# Communication.net
KiCad netlist of a schematic drawn in EAGLE
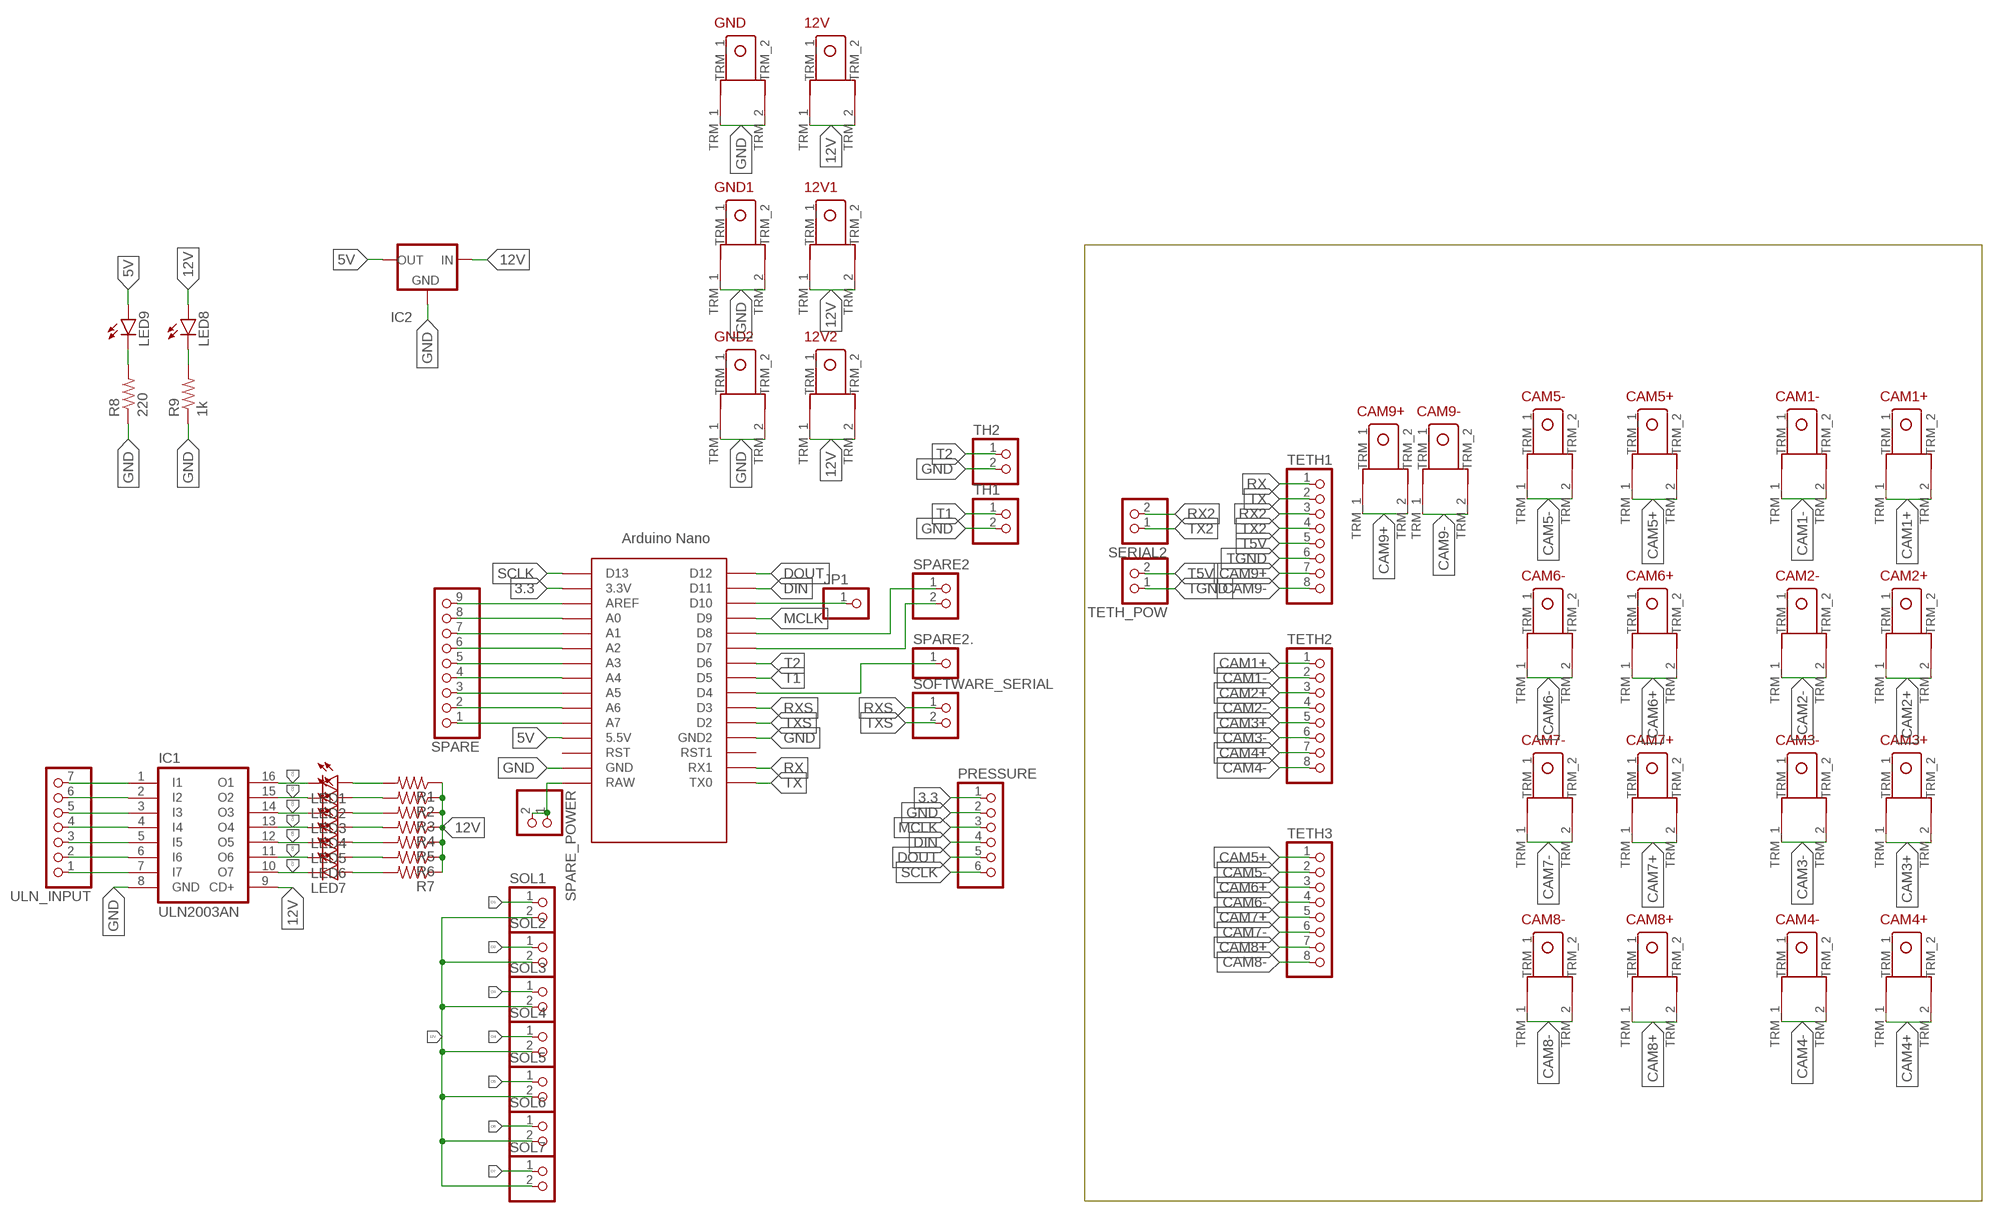
[diagram p0: schematic, sheet 1]

(export (version "E")
  (design (tool "Eeschema 10.0.6"))
  (components
    (comp (ref "12V")
      (value "TERMINAL_EDITED")
      (footprint "eagle-import:TERMINAL_EDITED")
      (libsource (lib "eagle-import") (part "TERMINAL_EDITED"))
    )
    (comp (ref "12V1")
      (value "TERMINAL_EDITED")
      (footprint "eagle-import:TERMINAL_EDITED")
      (libsource (lib "eagle-import") (part "TERMINAL_EDITED"))
    )
    (comp (ref "12V2")
      (value "TERMINAL_EDITED")
      (footprint "eagle-import:TERMINAL_EDITED")
      (libsource (lib "eagle-import") (part "TERMINAL_EDITED"))
    )
    (comp (ref "CAM1+")
      (value "TERMINAL_EDITED")
      (footprint "eagle-import:TERMINAL_EDITED")
      (libsource (lib "eagle-import") (part "TERMINAL_EDITED"))
    )
    (comp (ref "CAM1-")
      (value "TERMINAL_EDITED")
      (footprint "eagle-import:TERMINAL_EDITED")
      (libsource (lib "eagle-import") (part "TERMINAL_EDITED"))
    )
    (comp (ref "CAM2+")
      (value "TERMINAL_EDITED")
      (footprint "eagle-import:TERMINAL_EDITED")
      (libsource (lib "eagle-import") (part "TERMINAL_EDITED"))
    )
    (comp (ref "CAM2-")
      (value "TERMINAL_EDITED")
      (footprint "eagle-import:TERMINAL_EDITED")
      (libsource (lib "eagle-import") (part "TERMINAL_EDITED"))
    )
    (comp (ref "CAM3+")
      (value "TERMINAL_EDITED")
      (footprint "eagle-import:TERMINAL_EDITED")
      (libsource (lib "eagle-import") (part "TERMINAL_EDITED"))
    )
    (comp (ref "CAM3-")
      (value "TERMINAL_EDITED")
      (footprint "eagle-import:TERMINAL_EDITED")
      (libsource (lib "eagle-import") (part "TERMINAL_EDITED"))
    )
    (comp (ref "CAM4+")
      (value "TERMINAL_EDITED")
      (footprint "eagle-import:TERMINAL_EDITED")
      (libsource (lib "eagle-import") (part "TERMINAL_EDITED"))
    )
    (comp (ref "CAM4-")
      (value "TERMINAL_EDITED")
      (footprint "eagle-import:TERMINAL_EDITED")
      (libsource (lib "eagle-import") (part "TERMINAL_EDITED"))
    )
    (comp (ref "CAM5+")
      (value "TERMINAL_EDITED")
      (footprint "eagle-import:TERMINAL_EDITED")
      (libsource (lib "eagle-import") (part "TERMINAL_EDITED"))
    )
    (comp (ref "CAM5-")
      (value "TERMINAL_EDITED")
      (footprint "eagle-import:TERMINAL_EDITED")
      (libsource (lib "eagle-import") (part "TERMINAL_EDITED"))
    )
    (comp (ref "CAM6+")
      (value "TERMINAL_EDITED")
      (footprint "eagle-import:TERMINAL_EDITED")
      (libsource (lib "eagle-import") (part "TERMINAL_EDITED"))
    )
    (comp (ref "CAM6-")
      (value "TERMINAL_EDITED")
      (footprint "eagle-import:TERMINAL_EDITED")
      (libsource (lib "eagle-import") (part "TERMINAL_EDITED"))
    )
    (comp (ref "CAM7+")
      (value "TERMINAL_EDITED")
      (footprint "eagle-import:TERMINAL_EDITED")
      (libsource (lib "eagle-import") (part "TERMINAL_EDITED"))
    )
    (comp (ref "CAM7-")
      (value "TERMINAL_EDITED")
      (footprint "eagle-import:TERMINAL_EDITED")
      (libsource (lib "eagle-import") (part "TERMINAL_EDITED"))
    )
    (comp (ref "CAM8+")
      (value "TERMINAL_EDITED")
      (footprint "eagle-import:TERMINAL_EDITED")
      (libsource (lib "eagle-import") (part "TERMINAL_EDITED"))
    )
    (comp (ref "CAM8-")
      (value "TERMINAL_EDITED")
      (footprint "eagle-import:TERMINAL_EDITED")
      (libsource (lib "eagle-import") (part "TERMINAL_EDITED"))
    )
    (comp (ref "CAM9+")
      (value "TERMINAL_EDITED")
      (footprint "eagle-import:TERMINAL_EDITED")
      (libsource (lib "eagle-import") (part "MIA_LIBRARY-2-2-2_16672108_TERMINAL_EDITED"))
    )
    (comp (ref "CAM9-")
      (value "TERMINAL_EDITED")
      (footprint "eagle-import:TERMINAL_EDITED")
      (libsource (lib "eagle-import") (part "MIA_LIBRARY-2-2-2_16672108_TERMINAL_EDITED"))
    )
    (comp (ref "GND")
      (value "TERMINAL_EDITED")
      (footprint "eagle-import:TERMINAL_EDITED")
      (libsource (lib "eagle-import") (part "TERMINAL_EDITED"))
    )
    (comp (ref "GND1")
      (value "TERMINAL_EDITED")
      (footprint "eagle-import:TERMINAL_EDITED")
      (libsource (lib "eagle-import") (part "TERMINAL_EDITED"))
    )
    (comp (ref "GND2")
      (value "TERMINAL_EDITED")
      (footprint "eagle-import:TERMINAL_EDITED")
      (libsource (lib "eagle-import") (part "TERMINAL_EDITED"))
    )
    (comp (ref "IC1")
      (value "ULN2003AN")
      (footprint "eagle-import:DIL16")
      (libsource (lib "eagle-import") (part "ULN2003AN"))
    )
    (comp (ref "IC2")
      (value "78XX-METAL")
      (footprint "eagle-import:TO3-79")
      (libsource (lib "eagle-import") (part "78XX-METAL"))
    )
    (comp (ref "JP1")
      (value "PINHD-1X1")
      (footprint "eagle-import:1X01")
      (libsource (lib "eagle-import") (part "PINHD-1X1"))
    )
    (comp (ref "LED1")
      (value "LED5MM")
      (footprint "eagle-import:LED5MM")
      (libsource (lib "eagle-import") (part "LED5MM"))
    )
    (comp (ref "LED2")
      (value "LED5MM")
      (footprint "eagle-import:LED5MM")
      (libsource (lib "eagle-import") (part "LED5MM"))
    )
    (comp (ref "LED3")
      (value "LED5MM")
      (footprint "eagle-import:LED5MM")
      (libsource (lib "eagle-import") (part "LED5MM"))
    )
    (comp (ref "LED4")
      (value "LED5MM")
      (footprint "eagle-import:LED5MM")
      (libsource (lib "eagle-import") (part "LED5MM"))
    )
    (comp (ref "LED5")
      (value "LED5MM")
      (footprint "eagle-import:LED5MM")
      (libsource (lib "eagle-import") (part "LED5MM"))
    )
    (comp (ref "LED6")
      (value "LED5MM")
      (footprint "eagle-import:LED5MM")
      (libsource (lib "eagle-import") (part "LED5MM"))
    )
    (comp (ref "LED7")
      (value "LED5MM")
      (footprint "eagle-import:LED5MM")
      (libsource (lib "eagle-import") (part "LED5MM"))
    )
    (comp (ref "LED8")
      (value "LED5MM")
      (footprint "eagle-import:LED5MM")
      (libsource (lib "eagle-import") (part "LED5MM"))
    )
    (comp (ref "LED9")
      (value "LED5MM")
      (footprint "eagle-import:LED5MM")
      (libsource (lib "eagle-import") (part "LED5MM"))
    )
    (comp (ref "PRESSURE")
      (value "PINHD-6_DATA")
      (footprint "eagle-import:1X06_DATA")
      (libsource (lib "eagle-import") (part "PINHD-6_DATA"))
    )
    (comp (ref "R1")
      (value "R-US_0204/7")
      (footprint "eagle-import:0204_7")
      (libsource (lib "eagle-import") (part "R-US_0204/7"))
    )
    (comp (ref "R2")
      (value "R-US_0204/7")
      (footprint "eagle-import:0204_7")
      (libsource (lib "eagle-import") (part "R-US_0204/7"))
    )
    (comp (ref "R3")
      (value "R-US_0204/7")
      (footprint "eagle-import:0204_7")
      (libsource (lib "eagle-import") (part "R-US_0204/7"))
    )
    (comp (ref "R4")
      (value "R-US_0204/7")
      (footprint "eagle-import:0204_7")
      (libsource (lib "eagle-import") (part "R-US_0204/7"))
    )
    (comp (ref "R5")
      (value "R-US_0204/7")
      (footprint "eagle-import:0204_7")
      (libsource (lib "eagle-import") (part "R-US_0204/7"))
    )
    (comp (ref "R6")
      (value "R-US_0204/7")
      (footprint "eagle-import:0204_7")
      (libsource (lib "eagle-import") (part "R-US_0204/7"))
    )
    (comp (ref "R7")
      (value "R-US_0204/7")
      (footprint "eagle-import:0204_7")
      (libsource (lib "eagle-import") (part "R-US_0204/7"))
    )
    (comp (ref "R8")
      (value "220")
      (footprint "eagle-import:0204_7")
      (libsource (lib "eagle-import") (part "R-US_0204/7"))
    )
    (comp (ref "R9")
      (value "1k")
      (footprint "eagle-import:0204_7")
      (libsource (lib "eagle-import") (part "R-US_0204/7"))
    )
    (comp (ref "SERIAL2")
      (value "PINHD-2_DATA")
      (footprint "eagle-import:1X02_DATA")
      (libsource (lib "eagle-import") (part "PINHD-2_DATA"))
    )
    (comp (ref "SOFTWARE_SERIAL")
      (value "PINHD-2_DATA")
      (footprint "eagle-import:1X02_DATA")
      (libsource (lib "eagle-import") (part "PINHD-2_DATA"))
    )
    (comp (ref "SOL1")
      (value "PINHD-2_DATA")
      (footprint "eagle-import:1X02_DATA")
      (libsource (lib "eagle-import") (part "PINHD-2_DATA"))
    )
    (comp (ref "SOL2")
      (value "PINHD-2_DATA")
      (footprint "eagle-import:1X02_DATA")
      (libsource (lib "eagle-import") (part "PINHD-2_DATA"))
    )
    (comp (ref "SOL3")
      (value "PINHD-2_DATA")
      (footprint "eagle-import:1X02_DATA")
      (libsource (lib "eagle-import") (part "PINHD-2_DATA"))
    )
    (comp (ref "SOL4")
      (value "PINHD-2_DATA")
      (footprint "eagle-import:1X02_DATA")
      (libsource (lib "eagle-import") (part "PINHD-2_DATA"))
    )
    (comp (ref "SOL5")
      (value "PINHD-2_DATA")
      (footprint "eagle-import:1X02_DATA")
      (libsource (lib "eagle-import") (part "PINHD-2_DATA"))
    )
    (comp (ref "SOL6")
      (value "PINHD-2_DATA")
      (footprint "eagle-import:1X02_DATA")
      (libsource (lib "eagle-import") (part "PINHD-2_DATA"))
    )
    (comp (ref "SOL7")
      (value "PINHD-2_DATA")
      (footprint "eagle-import:1X02_DATA")
      (libsource (lib "eagle-import") (part "PINHD-2_DATA"))
    )
    (comp (ref "SPARE")
      (value "PINHD-1X9")
      (footprint "eagle-import:1X09")
      (libsource (lib "eagle-import") (part "PINHD-1X9"))
    )
    (comp (ref "SPARE2")
      (value "PINHD-2_DATA")
      (footprint "eagle-import:1X02_DATA")
      (libsource (lib "eagle-import") (part "PINHD-2_DATA"))
    )
    (comp (ref "SPARE2.")
      (value "PINHD-1X1")
      (footprint "eagle-import:1X01")
      (libsource (lib "eagle-import") (part "pinhead_mo_PINHD-1X1"))
    )
    (comp (ref "SPARE_POWER")
      (value "PINHD-2_DATA")
      (footprint "eagle-import:1X02_DATA")
      (libsource (lib "eagle-import") (part "PINHD-2_DATA"))
    )
    (comp (ref "TETH1")
      (value "PINHD-8_DATA")
      (footprint "eagle-import:1X08_DATA")
      (libsource (lib "eagle-import") (part "PINHD-8_DATA"))
    )
    (comp (ref "TETH2")
      (value "PINHD-8_DATA")
      (footprint "eagle-import:1X08_DATA")
      (libsource (lib "eagle-import") (part "PINHD-8_DATA"))
    )
    (comp (ref "TETH3")
      (value "PINHD-8_DATA")
      (footprint "eagle-import:1X08_DATA")
      (libsource (lib "eagle-import") (part "PINHD-8_DATA"))
    )
    (comp (ref "TETH_POW")
      (value "PINHD-2_DATA")
      (footprint "eagle-import:1X02_DATA")
      (libsource (lib "eagle-import") (part "PINHD-2_DATA"))
    )
    (comp (ref "TH1")
      (value "PINHD-2_DATA")
      (footprint "eagle-import:1X02_DATA")
      (libsource (lib "eagle-import") (part "PINHD-2_DATA"))
    )
    (comp (ref "TH2")
      (value "PINHD-2_DATA")
      (footprint "eagle-import:1X02_DATA")
      (libsource (lib "eagle-import") (part "PINHD-2_DATA"))
    )
    (comp (ref "U$1")
      (value "ARDUINO_NANO")
      (footprint "eagle-import:NANO")
      (libsource (lib "eagle-import") (part "ARDUINO_NANO"))
    )
    (comp (ref "ULN_INPUT")
      (value "PINHD-1X7")
      (footprint "eagle-import:1X07")
      (libsource (lib "eagle-import") (part "PINHD-1X7"))
    )
  )
  (nets
    (net (code "1") (name "3.3") (class "Default")
      (node (ref "PRESSURE") (pin "1") (pinfunction "1_1") (pintype "passive"))
      (node (ref "U$1") (pin "3.3V") (pinfunction "3.3V_3.3V") (pintype "bidirectional"))
    )
    (net (code "2") (name "5V") (class "Default")
      (node (ref "IC2") (pin "1") (pinfunction "OUT_1") (pintype "passive"))
      (node (ref "LED9") (pin "A") (pinfunction "A_A") (pintype "passive"))
      (node (ref "U$1") (pin "5V") (pinfunction "5.5V_5V") (pintype "bidirectional"))
    )
    (net (code "3") (name "12V") (class "Default")
      (node (ref "12V") (pin "TRM_1") (pinfunction "TRM_1_TRM_1") (pintype "bidirectional"))
      (node (ref "12V") (pin "TRM_2") (pinfunction "TRM_2_TRM_2") (pintype "bidirectional"))
      (node (ref "12V1") (pin "TRM_1") (pinfunction "TRM_1_TRM_1") (pintype "bidirectional"))
      (node (ref "12V1") (pin "TRM_2") (pinfunction "TRM_2_TRM_2") (pintype "bidirectional"))
      (node (ref "12V2") (pin "TRM_1") (pinfunction "TRM_1_TRM_1") (pintype "bidirectional"))
      (node (ref "12V2") (pin "TRM_2") (pinfunction "TRM_2_TRM_2") (pintype "bidirectional"))
      (node (ref "IC1") (pin "9") (pinfunction "CD+_9") (pintype "passive"))
      (node (ref "IC2") (pin "3") (pinfunction "IN_3") (pintype "input"))
      (node (ref "LED8") (pin "A") (pinfunction "A_A") (pintype "passive"))
      (node (ref "R1") (pin "1") (pinfunction "1_1") (pintype "passive"))
      (node (ref "R2") (pin "1") (pinfunction "1_1") (pintype "passive"))
      (node (ref "R3") (pin "1") (pinfunction "1_1") (pintype "passive"))
      (node (ref "R4") (pin "1") (pinfunction "1_1") (pintype "passive"))
      (node (ref "R5") (pin "1") (pinfunction "1_1") (pintype "passive"))
      (node (ref "R6") (pin "1") (pinfunction "1_1") (pintype "passive"))
      (node (ref "R7") (pin "1") (pinfunction "1_1") (pintype "passive"))
      (node (ref "SOL1") (pin "2") (pinfunction "2_2") (pintype "passive"))
      (node (ref "SOL2") (pin "2") (pinfunction "2_2") (pintype "passive"))
      (node (ref "SOL3") (pin "2") (pinfunction "2_2") (pintype "passive"))
      (node (ref "SOL4") (pin "2") (pinfunction "2_2") (pintype "passive"))
      (node (ref "SOL5") (pin "2") (pinfunction "2_2") (pintype "passive"))
      (node (ref "SOL6") (pin "2") (pinfunction "2_2") (pintype "passive"))
      (node (ref "SOL7") (pin "2") (pinfunction "2_2") (pintype "passive"))
    )
    (net (code "4") (name "CAM1+") (class "Default")
      (node (ref "CAM1+") (pin "TRM_1") (pinfunction "TRM_1_TRM_1") (pintype "bidirectional"))
      (node (ref "CAM1+") (pin "TRM_2") (pinfunction "TRM_2_TRM_2") (pintype "bidirectional"))
      (node (ref "TETH2") (pin "1") (pinfunction "1_1") (pintype "passive"))
    )
    (net (code "5") (name "CAM1-") (class "Default")
      (node (ref "CAM1-") (pin "TRM_1") (pinfunction "TRM_1_TRM_1") (pintype "bidirectional"))
      (node (ref "CAM1-") (pin "TRM_2") (pinfunction "TRM_2_TRM_2") (pintype "bidirectional"))
      (node (ref "TETH2") (pin "2") (pinfunction "2_2") (pintype "passive"))
    )
    (net (code "6") (name "CAM2+") (class "Default")
      (node (ref "CAM2+") (pin "TRM_1") (pinfunction "TRM_1_TRM_1") (pintype "bidirectional"))
      (node (ref "CAM2+") (pin "TRM_2") (pinfunction "TRM_2_TRM_2") (pintype "bidirectional"))
      (node (ref "TETH2") (pin "3") (pinfunction "3_3") (pintype "passive"))
    )
    (net (code "7") (name "CAM2-") (class "Default")
      (node (ref "CAM2-") (pin "TRM_1") (pinfunction "TRM_1_TRM_1") (pintype "bidirectional"))
      (node (ref "CAM2-") (pin "TRM_2") (pinfunction "TRM_2_TRM_2") (pintype "bidirectional"))
      (node (ref "TETH2") (pin "4") (pinfunction "4_4") (pintype "passive"))
    )
    (net (code "8") (name "CAM3+") (class "Default")
      (node (ref "CAM3+") (pin "TRM_1") (pinfunction "TRM_1_TRM_1") (pintype "bidirectional"))
      (node (ref "CAM3+") (pin "TRM_2") (pinfunction "TRM_2_TRM_2") (pintype "bidirectional"))
      (node (ref "TETH2") (pin "5") (pinfunction "5_5") (pintype "passive"))
    )
    (net (code "9") (name "CAM3-") (class "Default")
      (node (ref "CAM3-") (pin "TRM_1") (pinfunction "TRM_1_TRM_1") (pintype "bidirectional"))
      (node (ref "CAM3-") (pin "TRM_2") (pinfunction "TRM_2_TRM_2") (pintype "bidirectional"))
      (node (ref "TETH2") (pin "6") (pinfunction "6_6") (pintype "passive"))
    )
    (net (code "10") (name "CAM4+") (class "Default")
      (node (ref "CAM4+") (pin "TRM_1") (pinfunction "TRM_1_TRM_1") (pintype "bidirectional"))
      (node (ref "CAM4+") (pin "TRM_2") (pinfunction "TRM_2_TRM_2") (pintype "bidirectional"))
      (node (ref "TETH2") (pin "7") (pinfunction "7_7") (pintype "passive"))
    )
    (net (code "11") (name "CAM4-") (class "Default")
      (node (ref "CAM4-") (pin "TRM_1") (pinfunction "TRM_1_TRM_1") (pintype "bidirectional"))
      (node (ref "CAM4-") (pin "TRM_2") (pinfunction "TRM_2_TRM_2") (pintype "bidirectional"))
      (node (ref "TETH2") (pin "8") (pinfunction "8_8") (pintype "passive"))
    )
    (net (code "12") (name "CAM5+") (class "Default")
      (node (ref "CAM5+") (pin "TRM_1") (pinfunction "TRM_1_TRM_1") (pintype "bidirectional"))
      (node (ref "CAM5+") (pin "TRM_2") (pinfunction "TRM_2_TRM_2") (pintype "bidirectional"))
      (node (ref "TETH3") (pin "1") (pinfunction "1_1") (pintype "passive"))
    )
    (net (code "13") (name "CAM5-") (class "Default")
      (node (ref "CAM5-") (pin "TRM_1") (pinfunction "TRM_1_TRM_1") (pintype "bidirectional"))
      (node (ref "CAM5-") (pin "TRM_2") (pinfunction "TRM_2_TRM_2") (pintype "bidirectional"))
      (node (ref "TETH3") (pin "2") (pinfunction "2_2") (pintype "passive"))
    )
    (net (code "14") (name "CAM6+") (class "Default")
      (node (ref "CAM6+") (pin "TRM_1") (pinfunction "TRM_1_TRM_1") (pintype "bidirectional"))
      (node (ref "CAM6+") (pin "TRM_2") (pinfunction "TRM_2_TRM_2") (pintype "bidirectional"))
      (node (ref "TETH3") (pin "3") (pinfunction "3_3") (pintype "passive"))
    )
    (net (code "15") (name "CAM6-") (class "Default")
      (node (ref "CAM6-") (pin "TRM_1") (pinfunction "TRM_1_TRM_1") (pintype "bidirectional"))
      (node (ref "CAM6-") (pin "TRM_2") (pinfunction "TRM_2_TRM_2") (pintype "bidirectional"))
      (node (ref "TETH3") (pin "4") (pinfunction "4_4") (pintype "passive"))
    )
    (net (code "16") (name "CAM7+") (class "Default")
      (node (ref "CAM7+") (pin "TRM_1") (pinfunction "TRM_1_TRM_1") (pintype "bidirectional"))
      (node (ref "CAM7+") (pin "TRM_2") (pinfunction "TRM_2_TRM_2") (pintype "bidirectional"))
      (node (ref "TETH3") (pin "5") (pinfunction "5_5") (pintype "passive"))
    )
    (net (code "17") (name "CAM7-") (class "Default")
      (node (ref "CAM7-") (pin "TRM_1") (pinfunction "TRM_1_TRM_1") (pintype "bidirectional"))
      (node (ref "CAM7-") (pin "TRM_2") (pinfunction "TRM_2_TRM_2") (pintype "bidirectional"))
      (node (ref "TETH3") (pin "6") (pinfunction "6_6") (pintype "passive"))
    )
    (net (code "18") (name "CAM8+") (class "Default")
      (node (ref "CAM8+") (pin "TRM_1") (pinfunction "TRM_1_TRM_1") (pintype "bidirectional"))
      (node (ref "CAM8+") (pin "TRM_2") (pinfunction "TRM_2_TRM_2") (pintype "bidirectional"))
      (node (ref "TETH3") (pin "7") (pinfunction "7_7") (pintype "passive"))
    )
    (net (code "19") (name "CAM8-") (class "Default")
      (node (ref "CAM8-") (pin "TRM_1") (pinfunction "TRM_1_TRM_1") (pintype "bidirectional"))
      (node (ref "CAM8-") (pin "TRM_2") (pinfunction "TRM_2_TRM_2") (pintype "bidirectional"))
      (node (ref "TETH3") (pin "8") (pinfunction "8_8") (pintype "passive"))
    )
    (net (code "20") (name "CAM9+") (class "Default")
      (node (ref "CAM9+") (pin "TRM_1") (pinfunction "TRM_1_TRM_1") (pintype "bidirectional"))
      (node (ref "CAM9+") (pin "TRM_2") (pinfunction "TRM_2_TRM_2") (pintype "bidirectional"))
      (node (ref "TETH1") (pin "7") (pinfunction "7_7") (pintype "passive"))
    )
    (net (code "21") (name "CAM9-") (class "Default")
      (node (ref "CAM9-") (pin "TRM_1") (pinfunction "TRM_1_TRM_1") (pintype "bidirectional"))
      (node (ref "CAM9-") (pin "TRM_2") (pinfunction "TRM_2_TRM_2") (pintype "bidirectional"))
      (node (ref "TETH1") (pin "8") (pinfunction "8_8") (pintype "passive"))
    )
    (net (code "22") (name "DIN") (class "Default")
      (node (ref "PRESSURE") (pin "4") (pinfunction "4_4") (pintype "passive"))
      (node (ref "U$1") (pin "D11") (pinfunction "D11_D11") (pintype "bidirectional"))
    )
    (net (code "23") (name "DOUT") (class "Default")
      (node (ref "PRESSURE") (pin "5") (pinfunction "5_5") (pintype "passive"))
      (node (ref "U$1") (pin "D12") (pinfunction "D12_D12") (pintype "bidirectional"))
    )
    (net (code "24") (name "GND") (class "Default")
      (node (ref "GND") (pin "TRM_1") (pinfunction "TRM_1_TRM_1") (pintype "bidirectional"))
      (node (ref "GND") (pin "TRM_2") (pinfunction "TRM_2_TRM_2") (pintype "bidirectional"))
      (node (ref "GND1") (pin "TRM_1") (pinfunction "TRM_1_TRM_1") (pintype "bidirectional"))
      (node (ref "GND1") (pin "TRM_2") (pinfunction "TRM_2_TRM_2") (pintype "bidirectional"))
      (node (ref "GND2") (pin "TRM_1") (pinfunction "TRM_1_TRM_1") (pintype "bidirectional"))
      (node (ref "GND2") (pin "TRM_2") (pinfunction "TRM_2_TRM_2") (pintype "bidirectional"))
      (node (ref "IC1") (pin "8") (pinfunction "GND_8") (pintype "power_in"))
      (node (ref "IC2") (pin "2") (pinfunction "GND_2") (pintype "input"))
      (node (ref "PRESSURE") (pin "2") (pinfunction "2_2") (pintype "passive"))
      (node (ref "R8") (pin "1") (pinfunction "1_1") (pintype "passive"))
      (node (ref "R9") (pin "1") (pinfunction "1_1") (pintype "passive"))
      (node (ref "TH1") (pin "2") (pinfunction "2_2") (pintype "passive"))
      (node (ref "TH2") (pin "2") (pinfunction "2_2") (pintype "passive"))
      (node (ref "U$1") (pin "GND") (pinfunction "GND_GND") (pintype "bidirectional"))
      (node (ref "U$1") (pin "GND1") (pinfunction "GND2_GND1") (pintype "bidirectional"))
    )
    (net (code "25") (name "MCLK") (class "Default")
      (node (ref "PRESSURE") (pin "3") (pinfunction "3_3") (pintype "passive"))
      (node (ref "U$1") (pin "D9") (pinfunction "D9_D9") (pintype "bidirectional"))
    )
    (net (code "26") (name "Net-(IC1-I1)") (class "Default")
      (node (ref "IC1") (pin "1") (pinfunction "I1_1") (pintype "input"))
      (node (ref "ULN_INPUT") (pin "7") (pinfunction "7_7") (pintype "passive"))
    )
    (net (code "27") (name "Net-(IC1-I2)") (class "Default")
      (node (ref "IC1") (pin "2") (pinfunction "I2_2") (pintype "input"))
      (node (ref "ULN_INPUT") (pin "6") (pinfunction "6_6") (pintype "passive"))
    )
    (net (code "28") (name "Net-(IC1-I3)") (class "Default")
      (node (ref "IC1") (pin "3") (pinfunction "I3_3") (pintype "input"))
      (node (ref "ULN_INPUT") (pin "5") (pinfunction "5_5") (pintype "passive"))
    )
    (net (code "29") (name "Net-(IC1-I4)") (class "Default")
      (node (ref "IC1") (pin "4") (pinfunction "I4_4") (pintype "input"))
      (node (ref "ULN_INPUT") (pin "4") (pinfunction "4_4") (pintype "passive"))
    )
    (net (code "30") (name "Net-(IC1-I5)") (class "Default")
      (node (ref "IC1") (pin "5") (pinfunction "I5_5") (pintype "input"))
      (node (ref "ULN_INPUT") (pin "3") (pinfunction "3_3") (pintype "passive"))
    )
    (net (code "31") (name "Net-(IC1-I6)") (class "Default")
      (node (ref "IC1") (pin "6") (pinfunction "I6_6") (pintype "input"))
      (node (ref "ULN_INPUT") (pin "2") (pinfunction "2_2") (pintype "passive"))
    )
    (net (code "32") (name "Net-(IC1-I7)") (class "Default")
      (node (ref "IC1") (pin "7") (pinfunction "I7_7") (pintype "input"))
      (node (ref "ULN_INPUT") (pin "1") (pinfunction "1_1") (pintype "passive"))
    )
    (net (code "33") (name "Net-(JP1-Pad1)") (class "Default")
      (node (ref "JP1") (pin "1") (pinfunction "1_1") (pintype "passive"))
      (node (ref "U$1") (pin "D10") (pinfunction "D10_D10") (pintype "bidirectional"))
    )
    (net (code "34") (name "Net-(LED1-PadA)") (class "Default")
      (node (ref "LED1") (pin "A") (pinfunction "A_A") (pintype "passive"))
      (node (ref "R1") (pin "2") (pinfunction "2_2") (pintype "passive"))
    )
    (net (code "35") (name "Net-(LED2-PadA)") (class "Default")
      (node (ref "LED2") (pin "A") (pinfunction "A_A") (pintype "passive"))
      (node (ref "R2") (pin "2") (pinfunction "2_2") (pintype "passive"))
    )
    (net (code "36") (name "Net-(LED3-PadA)") (class "Default")
      (node (ref "LED3") (pin "A") (pinfunction "A_A") (pintype "passive"))
      (node (ref "R3") (pin "2") (pinfunction "2_2") (pintype "passive"))
    )
    (net (code "37") (name "Net-(LED4-PadA)") (class "Default")
      (node (ref "LED4") (pin "A") (pinfunction "A_A") (pintype "passive"))
      (node (ref "R4") (pin "2") (pinfunction "2_2") (pintype "passive"))
    )
    (net (code "38") (name "Net-(LED5-PadA)") (class "Default")
      (node (ref "LED5") (pin "A") (pinfunction "A_A") (pintype "passive"))
      (node (ref "R5") (pin "2") (pinfunction "2_2") (pintype "passive"))
    )
    (net (code "39") (name "Net-(LED6-PadA)") (class "Default")
      (node (ref "LED6") (pin "A") (pinfunction "A_A") (pintype "passive"))
      (node (ref "R6") (pin "2") (pinfunction "2_2") (pintype "passive"))
    )
    (net (code "40") (name "Net-(LED7-PadA)") (class "Default")
      (node (ref "LED7") (pin "A") (pinfunction "A_A") (pintype "passive"))
      (node (ref "R7") (pin "2") (pinfunction "2_2") (pintype "passive"))
    )
    (net (code "41") (name "Net-(LED8-C)") (class "Default")
      (node (ref "LED8") (pin "K") (pinfunction "C_K") (pintype "passive"))
      (node (ref "R9") (pin "2") (pinfunction "2_2") (pintype "passive"))
    )
    (net (code "42") (name "Net-(LED9-C)") (class "Default")
      (node (ref "LED9") (pin "K") (pinfunction "C_K") (pintype "passive"))
      (node (ref "R8") (pin "2") (pinfunction "2_2") (pintype "passive"))
    )
    (net (code "43") (name "Net-(SPARE-Pad1)") (class "Default")
      (node (ref "SPARE") (pin "1") (pinfunction "1_1") (pintype "passive"))
      (node (ref "U$1") (pin "A7") (pinfunction "A7_A7") (pintype "bidirectional"))
    )
    (net (code "44") (name "Net-(SPARE-Pad2)") (class "Default")
      (node (ref "SPARE") (pin "2") (pinfunction "2_2") (pintype "passive"))
      (node (ref "U$1") (pin "A6") (pinfunction "A6_A6") (pintype "bidirectional"))
    )
    (net (code "45") (name "Net-(SPARE-Pad3)") (class "Default")
      (node (ref "SPARE") (pin "3") (pinfunction "3_3") (pintype "passive"))
      (node (ref "U$1") (pin "A5") (pinfunction "A5_A5") (pintype "bidirectional"))
    )
    (net (code "46") (name "Net-(SPARE-Pad4)") (class "Default")
      (node (ref "SPARE") (pin "4") (pinfunction "4_4") (pintype "passive"))
      (node (ref "U$1") (pin "A4") (pinfunction "A4_A4") (pintype "bidirectional"))
    )
    (net (code "47") (name "Net-(SPARE-Pad5)") (class "Default")
      (node (ref "SPARE") (pin "5") (pinfunction "5_5") (pintype "passive"))
      (node (ref "U$1") (pin "A3") (pinfunction "A3_A3") (pintype "bidirectional"))
    )
    (net (code "48") (name "Net-(SPARE-Pad6)") (class "Default")
      (node (ref "SPARE") (pin "6") (pinfunction "6_6") (pintype "passive"))
      (node (ref "U$1") (pin "A2") (pinfunction "A2_A2") (pintype "bidirectional"))
    )
    (net (code "49") (name "Net-(SPARE-Pad7)") (class "Default")
      (node (ref "SPARE") (pin "7") (pinfunction "7_7") (pintype "passive"))
      (node (ref "U$1") (pin "A1") (pinfunction "A1_A1") (pintype "bidirectional"))
    )
    (net (code "50") (name "Net-(SPARE-Pad8)") (class "Default")
      (node (ref "SPARE") (pin "8") (pinfunction "8_8") (pintype "passive"))
      (node (ref "U$1") (pin "A0") (pinfunction "A0_A0") (pintype "bidirectional"))
    )
    (net (code "51") (name "Net-(SPARE-Pad9)") (class "Default")
      (node (ref "SPARE") (pin "9") (pinfunction "9_9") (pintype "passive"))
      (node (ref "U$1") (pin "AREF") (pinfunction "AREF_AREF") (pintype "bidirectional"))
    )
    (net (code "52") (name "Net-(SPARE2-Pad1)") (class "Default")
      (node (ref "SPARE2") (pin "1") (pinfunction "1_1") (pintype "passive"))
      (node (ref "U$1") (pin "D8") (pinfunction "D8_D8") (pintype "bidirectional"))
    )
    (net (code "53") (name "Net-(SPARE2-Pad2)") (class "Default")
      (node (ref "SPARE2") (pin "2") (pinfunction "2_2") (pintype "passive"))
      (node (ref "U$1") (pin "D7") (pinfunction "D7_D7") (pintype "bidirectional"))
    )
    (net (code "54") (name "Net-(SPARE2.-Pad1)") (class "Default")
      (node (ref "SPARE2.") (pin "1") (pinfunction "1_1") (pintype "passive"))
      (node (ref "U$1") (pin "D4") (pinfunction "D4_D4") (pintype "bidirectional"))
    )
    (net (code "55") (name "Net-(SPARE_POWER-Pad1)") (class "Default")
      (node (ref "SPARE_POWER") (pin "1") (pinfunction "1_1") (pintype "passive"))
      (node (ref "SPARE_POWER") (pin "2") (pinfunction "2_2") (pintype "passive"))
      (node (ref "U$1") (pin "RAW") (pinfunction "RAW_RAW") (pintype "bidirectional"))
    )
    (net (code "56") (name "O1") (class "Default")
      (node (ref "IC1") (pin "16") (pinfunction "O1_16") (pintype "open_collector"))
      (node (ref "LED1") (pin "K") (pinfunction "C_K") (pintype "passive"))
      (node (ref "SOL1") (pin "1") (pinfunction "1_1") (pintype "passive"))
    )
    (net (code "57") (name "O2") (class "Default")
      (node (ref "IC1") (pin "15") (pinfunction "O2_15") (pintype "open_collector"))
      (node (ref "LED2") (pin "K") (pinfunction "C_K") (pintype "passive"))
      (node (ref "SOL2") (pin "1") (pinfunction "1_1") (pintype "passive"))
    )
    (net (code "58") (name "O3") (class "Default")
      (node (ref "IC1") (pin "14") (pinfunction "O3_14") (pintype "open_collector"))
      (node (ref "LED3") (pin "K") (pinfunction "C_K") (pintype "passive"))
      (node (ref "SOL3") (pin "1") (pinfunction "1_1") (pintype "passive"))
    )
    (net (code "59") (name "O4") (class "Default")
      (node (ref "IC1") (pin "13") (pinfunction "O4_13") (pintype "open_collector"))
      (node (ref "LED4") (pin "K") (pinfunction "C_K") (pintype "passive"))
      (node (ref "SOL4") (pin "1") (pinfunction "1_1") (pintype "passive"))
    )
    (net (code "60") (name "O5") (class "Default")
      (node (ref "IC1") (pin "12") (pinfunction "O5_12") (pintype "open_collector"))
      (node (ref "LED5") (pin "K") (pinfunction "C_K") (pintype "passive"))
      (node (ref "SOL5") (pin "1") (pinfunction "1_1") (pintype "passive"))
    )
    (net (code "61") (name "O6") (class "Default")
      (node (ref "IC1") (pin "11") (pinfunction "O6_11") (pintype "open_collector"))
      (node (ref "LED6") (pin "K") (pinfunction "C_K") (pintype "passive"))
      (node (ref "SOL6") (pin "1") (pinfunction "1_1") (pintype "passive"))
    )
    (net (code "62") (name "O7") (class "Default")
      (node (ref "IC1") (pin "10") (pinfunction "O7_10") (pintype "open_collector"))
      (node (ref "LED7") (pin "K") (pinfunction "C_K") (pintype "passive"))
      (node (ref "SOL7") (pin "1") (pinfunction "1_1") (pintype "passive"))
    )
    (net (code "63") (name "RX") (class "Default")
      (node (ref "TETH1") (pin "1") (pinfunction "1_1") (pintype "passive"))
      (node (ref "U$1") (pin "RX1") (pinfunction "RX1_RX1") (pintype "bidirectional"))
    )
    (net (code "64") (name "RX2") (class "Default")
      (node (ref "SERIAL2") (pin "2") (pinfunction "2_2") (pintype "passive"))
      (node (ref "TETH1") (pin "3") (pinfunction "3_3") (pintype "passive"))
    )
    (net (code "65") (name "RXS") (class "Default")
      (node (ref "SOFTWARE_SERIAL") (pin "1") (pinfunction "1_1") (pintype "passive"))
      (node (ref "U$1") (pin "D3") (pinfunction "D3_D3") (pintype "bidirectional"))
    )
    (net (code "66") (name "SCLK") (class "Default")
      (node (ref "PRESSURE") (pin "6") (pinfunction "6_6") (pintype "passive"))
      (node (ref "U$1") (pin "D13") (pinfunction "D13_D13") (pintype "bidirectional"))
    )
    (net (code "67") (name "T1") (class "Default")
      (node (ref "TH1") (pin "1") (pinfunction "1_1") (pintype "passive"))
      (node (ref "U$1") (pin "D5") (pinfunction "D5_D5") (pintype "bidirectional"))
    )
    (net (code "68") (name "T2") (class "Default")
      (node (ref "TH2") (pin "1") (pinfunction "1_1") (pintype "passive"))
      (node (ref "U$1") (pin "D6") (pinfunction "D6_D6") (pintype "bidirectional"))
    )
    (net (code "69") (name "T5V") (class "Default")
      (node (ref "TETH1") (pin "5") (pinfunction "5_5") (pintype "passive"))
      (node (ref "TETH_POW") (pin "2") (pinfunction "2_2") (pintype "passive"))
    )
    (net (code "70") (name "TGND") (class "Default")
      (node (ref "TETH1") (pin "6") (pinfunction "6_6") (pintype "passive"))
      (node (ref "TETH_POW") (pin "1") (pinfunction "1_1") (pintype "passive"))
    )
    (net (code "71") (name "TX") (class "Default")
      (node (ref "TETH1") (pin "2") (pinfunction "2_2") (pintype "passive"))
      (node (ref "U$1") (pin "TX0") (pinfunction "TX0_TX0") (pintype "bidirectional"))
    )
    (net (code "72") (name "TX2") (class "Default")
      (node (ref "SERIAL2") (pin "1") (pinfunction "1_1") (pintype "passive"))
      (node (ref "TETH1") (pin "4") (pinfunction "4_4") (pintype "passive"))
    )
    (net (code "73") (name "TXS") (class "Default")
      (node (ref "SOFTWARE_SERIAL") (pin "2") (pinfunction "2_2") (pintype "passive"))
      (node (ref "U$1") (pin "D2") (pinfunction "D2_D2") (pintype "bidirectional"))
    )
    (net (code "74") (name "unconnected-(U$1-PadRST)") (class "Default")
      (node (ref "U$1") (pin "RST") (pinfunction "RST_RST") (pintype "bidirectional"))
    )
    (net (code "75") (name "unconnected-(U$1-PadRST1)") (class "Default")
      (node (ref "U$1") (pin "RST1") (pinfunction "RST1_RST1") (pintype "bidirectional"))
    )
  )
)
